# Xadow_SD.net
KiCad netlist of a schematic drawn in EAGLE
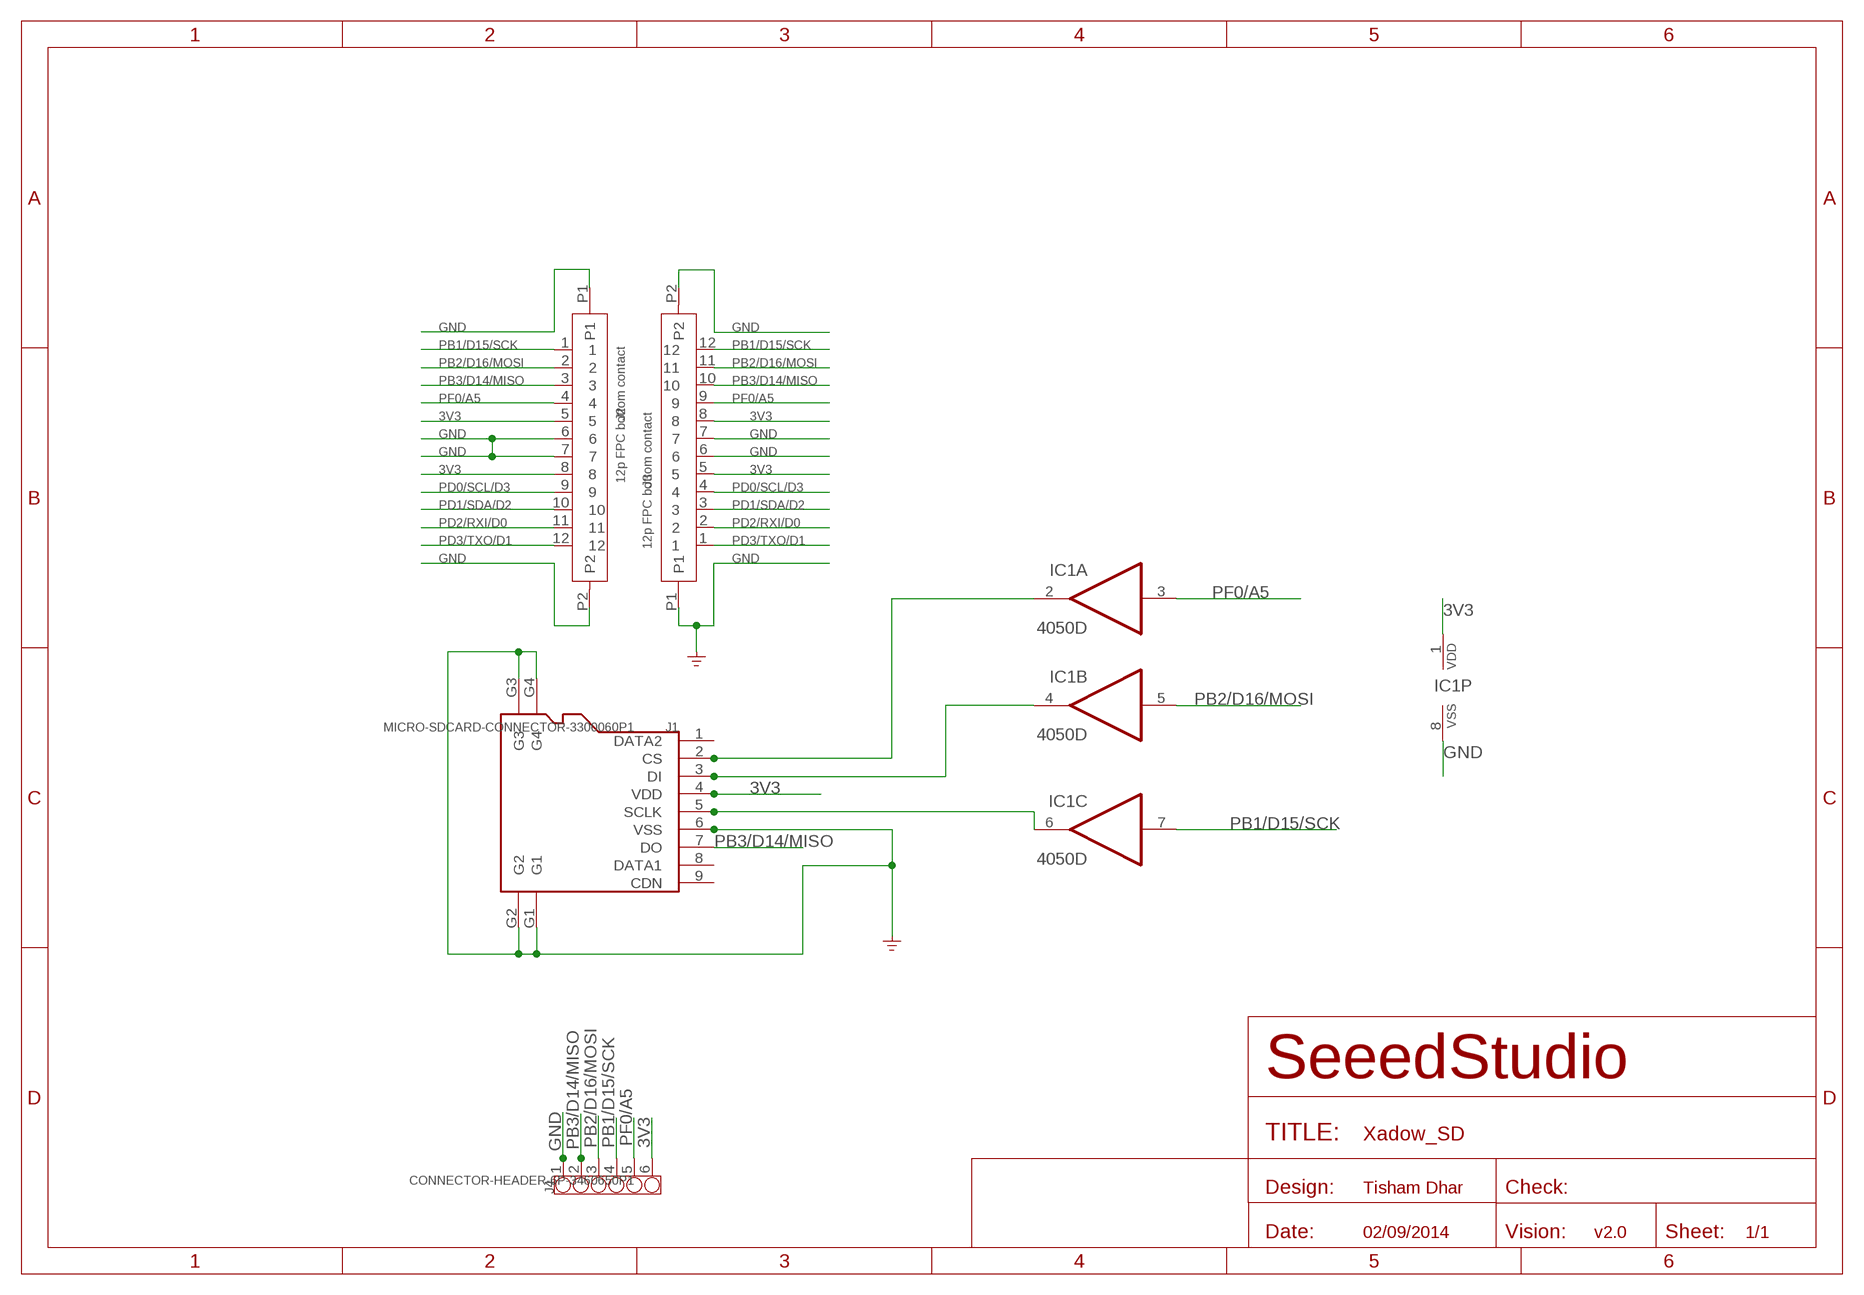
[diagram p0: schematic, sheet 1]

(export (version "E")
  (design (tool "Eeschema 10.0.6"))
  (components
    (comp (ref "IC1")
      (value "4050D")
      (footprint "eagle-import:SO16")
      (libsource (lib "eagle-import") (part "4050D"))
    )
    (comp (ref "J1")
      (value "MICRO-SDCARD-CONNECTOR-3300060P1")
      (footprint "eagle-import:9P-SMD-W-RING")
      (libsource (lib "eagle-import") (part "MICRO-SDCARD-CONNECTOR-3300060P1"))
    )
    (comp (ref "J2")
      (value "12p FPC bottom contact")
      (footprint "eagle-import:12P-0.5")
      (libsource (lib "eagle-import") (part "FPC052002-12LT"))
    )
    (comp (ref "J3")
      (value "12p FPC bottom contact")
      (footprint "eagle-import:12P-0.5")
      (libsource (lib "eagle-import") (part "FPC052002-12LT"))
    )
    (comp (ref "J4")
      (value "CONNECTOR-HEADER-6P-3460650P1")
      (footprint "eagle-import:1X6P-2.54-2.54-11.6-3.0-BLACK-MALE")
      (libsource (lib "eagle-import") (part "CONNECTOR-HEADER-6P-3460650P1"))
    )
  )
  (nets
    (net (code "1") (name "/3V3") (class "Default")
      (node (ref "IC1") (pin "1") (pinfunction "VDD_1") (pintype "power_in"))
      (node (ref "J1") (pin "4") (pinfunction "VDD_4") (pintype "bidirectional"))
      (node (ref "J2") (pin "5") (pinfunction "5_5") (pintype "bidirectional"))
      (node (ref "J2") (pin "8") (pinfunction "8_8") (pintype "bidirectional"))
      (node (ref "J3") (pin "5") (pinfunction "5_5") (pintype "bidirectional"))
      (node (ref "J3") (pin "8") (pinfunction "8_8") (pintype "bidirectional"))
      (node (ref "J4") (pin "6") (pinfunction "6_6") (pintype "bidirectional"))
    )
    (net (code "2") (name "/PB1{slash}D15{slash}SCK") (class "Default")
      (node (ref "IC1") (pin "7") (pinfunction "I_7") (pintype "input"))
      (node (ref "J2") (pin "1") (pinfunction "1_1") (pintype "bidirectional"))
      (node (ref "J3") (pin "12") (pinfunction "12_12") (pintype "bidirectional"))
      (node (ref "J4") (pin "4") (pinfunction "4_4") (pintype "bidirectional"))
    )
    (net (code "3") (name "/PB2{slash}D16{slash}MOSI") (class "Default")
      (node (ref "IC1") (pin "5") (pinfunction "I_5") (pintype "input"))
      (node (ref "J2") (pin "2") (pinfunction "2_2") (pintype "bidirectional"))
      (node (ref "J3") (pin "11") (pinfunction "11_11") (pintype "bidirectional"))
      (node (ref "J4") (pin "3") (pinfunction "3_3") (pintype "bidirectional"))
    )
    (net (code "4") (name "/PB3{slash}D14{slash}MISO") (class "Default")
      (node (ref "J1") (pin "7") (pinfunction "DO_7") (pintype "bidirectional"))
      (node (ref "J2") (pin "3") (pinfunction "3_3") (pintype "bidirectional"))
      (node (ref "J3") (pin "10") (pinfunction "10_10") (pintype "bidirectional"))
      (node (ref "J4") (pin "2") (pinfunction "2_2") (pintype "bidirectional"))
    )
    (net (code "5") (name "/PD0{slash}SCL{slash}D3") (class "Default")
      (node (ref "J2") (pin "9") (pinfunction "9_9") (pintype "bidirectional"))
      (node (ref "J3") (pin "4") (pinfunction "4_4") (pintype "bidirectional"))
    )
    (net (code "6") (name "/PD1{slash}SDA{slash}D2") (class "Default")
      (node (ref "J2") (pin "10") (pinfunction "10_10") (pintype "bidirectional"))
      (node (ref "J3") (pin "3") (pinfunction "3_3") (pintype "bidirectional"))
    )
    (net (code "7") (name "/PD2{slash}RXI{slash}D0") (class "Default")
      (node (ref "J2") (pin "11") (pinfunction "11_11") (pintype "bidirectional"))
      (node (ref "J3") (pin "2") (pinfunction "2_2") (pintype "bidirectional"))
    )
    (net (code "8") (name "/PD3{slash}TXO{slash}D1") (class "Default")
      (node (ref "J2") (pin "12") (pinfunction "12_12") (pintype "bidirectional"))
      (node (ref "J3") (pin "1") (pinfunction "1_1") (pintype "bidirectional"))
    )
    (net (code "9") (name "/PF0{slash}A5") (class "Default")
      (node (ref "IC1") (pin "3") (pinfunction "I_3") (pintype "input"))
      (node (ref "J2") (pin "4") (pinfunction "4_4") (pintype "bidirectional"))
      (node (ref "J3") (pin "9") (pinfunction "9_9") (pintype "bidirectional"))
      (node (ref "J4") (pin "5") (pinfunction "5_5") (pintype "bidirectional"))
    )
    (net (code "10") (name "GND_POWER") (class "Default")
      (node (ref "IC1") (pin "8") (pinfunction "VSS_8") (pintype "power_in"))
      (node (ref "J1") (pin "6") (pinfunction "VSS_6") (pintype "bidirectional"))
      (node (ref "J1") (pin "G1") (pinfunction "G1_G1") (pintype "bidirectional"))
      (node (ref "J1") (pin "G2") (pinfunction "G2_G2") (pintype "bidirectional"))
      (node (ref "J1") (pin "G3") (pinfunction "G3_G3") (pintype "bidirectional"))
      (node (ref "J1") (pin "G4") (pinfunction "G4_G4") (pintype "bidirectional"))
      (node (ref "J2") (pin "6") (pinfunction "6_6") (pintype "bidirectional"))
      (node (ref "J2") (pin "7") (pinfunction "7_7") (pintype "bidirectional"))
      (node (ref "J2") (pin "P1") (pinfunction "P1_P1") (pintype "bidirectional"))
      (node (ref "J2") (pin "P2") (pinfunction "P2_P2") (pintype "bidirectional"))
      (node (ref "J3") (pin "6") (pinfunction "6_6") (pintype "bidirectional"))
      (node (ref "J3") (pin "7") (pinfunction "7_7") (pintype "bidirectional"))
      (node (ref "J3") (pin "P1") (pinfunction "P1_P1") (pintype "bidirectional"))
      (node (ref "J3") (pin "P2") (pinfunction "P2_P2") (pintype "bidirectional"))
      (node (ref "J4") (pin "1") (pinfunction "1_1") (pintype "bidirectional"))
    )
    (net (code "11") (name "Net-(IC1A-O)") (class "Default")
      (node (ref "IC1") (pin "2") (pinfunction "O_2") (pintype "output"))
      (node (ref "J1") (pin "2") (pinfunction "CS_2") (pintype "bidirectional"))
    )
    (net (code "12") (name "Net-(IC1B-O)") (class "Default")
      (node (ref "IC1") (pin "4") (pinfunction "O_4") (pintype "output"))
      (node (ref "J1") (pin "3") (pinfunction "DI_3") (pintype "bidirectional"))
    )
    (net (code "13") (name "Net-(IC1C-O)") (class "Default")
      (node (ref "IC1") (pin "6") (pinfunction "O_6") (pintype "output"))
      (node (ref "J1") (pin "5") (pinfunction "SCLK_5") (pintype "bidirectional"))
    )
    (net (code "14") (name "unconnected-(J1-CDN-Pad9)") (class "Default")
      (node (ref "J1") (pin "9") (pinfunction "CDN_9") (pintype "bidirectional"))
    )
    (net (code "15") (name "unconnected-(J1-DATA1-Pad8)") (class "Default")
      (node (ref "J1") (pin "8") (pinfunction "DATA1_8") (pintype "bidirectional"))
    )
    (net (code "16") (name "unconnected-(J1-DATA2-Pad1)") (class "Default")
      (node (ref "J1") (pin "1") (pinfunction "DATA2_1") (pintype "bidirectional"))
    )
  )
)
